# Scheme.net
KiCad netlist of a schematic drawn in Altium Designer
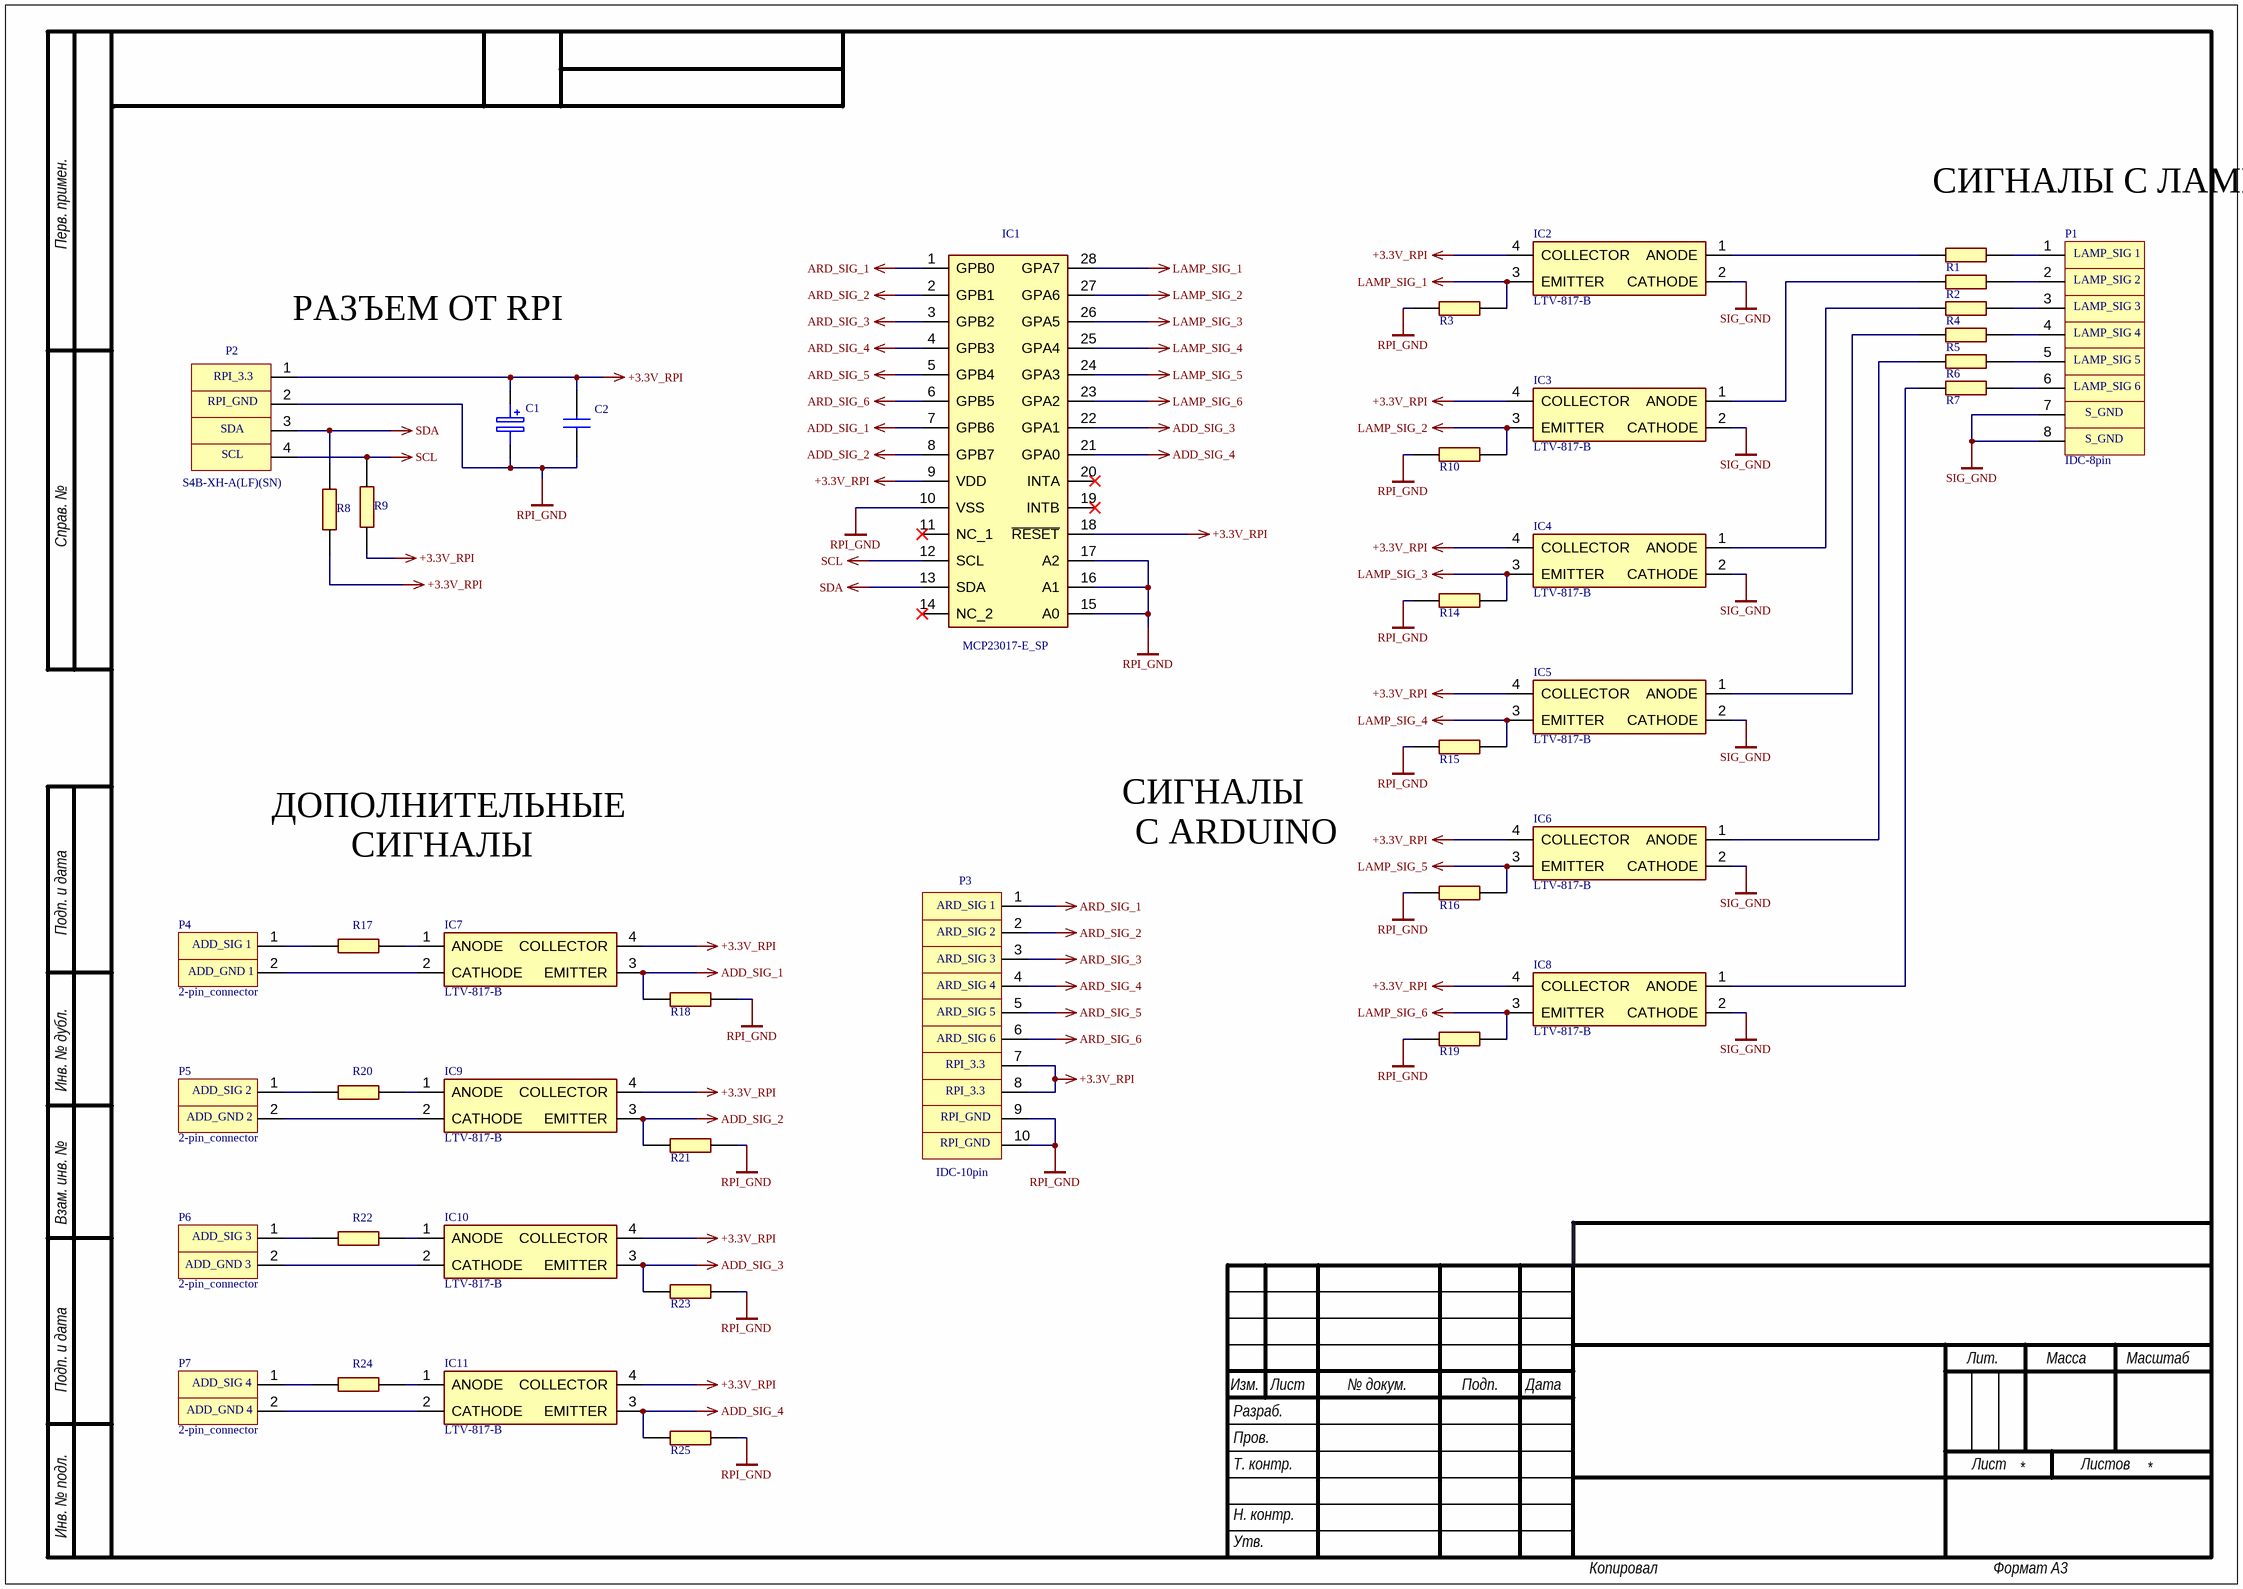
[diagram p0: Scheme.SchDoc]

(export (version "E")
  (design (tool "Eeschema 10.0.6"))
  (components
    (comp (ref "C1")
      (value "EEU-FR1V330")
      (footprint "PcbLib:CAPPRD200W55D500H1250")
      (description "Capacitor Polarised")
      (fields (field (name "MOUSER PART NUMBER") "667-EEU-FR1V330"))
      (libsource (lib "Schlib") (part "EEU-FR1V330"))
    )
    (comp (ref "C2")
      (value "C3216C0G1H683J160AE")
      (footprint "PcbLib:CAPC3216X180N")
      (description "Capacitor")
      (fields (field (name "MOUSER PART NUMBER") "810-C3216C0G1H683J16"))
      (libsource (lib "Schlib") (part "C3216C0G1H683J160AE"))
    )
    (comp (ref "IC1")
      (value "MCP23017-E_SP")
      (footprint "PcbLib:DIP794W56P254L3486H508Q28N")
      (description "Integrated Circuit")
      (fields
        (field (name "MANUFACTURER_PART_NUMBER") "MCP23017-E/SP")
        (field (name "MOUSER PART NUMBER") "579-MCP23017-E/SP")
      )
      (libsource (lib "Schlib") (part "MCP23017-E_SP"))
    )
    (comp (ref "IC2")
      (value "LTV-817-B")
      (footprint "PcbLib:DIP762W60P254L460H420Q4N")
      (description "Integrated Circuit")
      (libsource (lib "Schlib") (part "LTV-817-B"))
    )
    (comp (ref "IC3")
      (value "LTV-817-B")
      (footprint "PcbLib:DIP762W60P254L460H420Q4N")
      (description "Integrated Circuit")
      (libsource (lib "Schlib") (part "LTV-817-B"))
    )
    (comp (ref "IC4")
      (value "LTV-817-B")
      (footprint "PcbLib:DIP762W60P254L460H420Q4N")
      (description "Integrated Circuit")
      (libsource (lib "Schlib") (part "LTV-817-B"))
    )
    (comp (ref "IC5")
      (value "LTV-817-B")
      (footprint "PcbLib:DIP762W60P254L460H420Q4N")
      (description "Integrated Circuit")
      (libsource (lib "Schlib") (part "LTV-817-B"))
    )
    (comp (ref "IC6")
      (value "LTV-817-B")
      (footprint "PcbLib:DIP762W60P254L460H420Q4N")
      (description "Integrated Circuit")
      (libsource (lib "Schlib") (part "LTV-817-B"))
    )
    (comp (ref "IC7")
      (value "LTV-817-B")
      (footprint "PcbLib:DIP762W60P254L460H420Q4N")
      (description "Integrated Circuit")
      (libsource (lib "") (part "LTV-817-B_1"))
    )
    (comp (ref "IC8")
      (value "LTV-817-B")
      (footprint "PcbLib:DIP762W60P254L460H420Q4N")
      (description "Integrated Circuit")
      (libsource (lib "Schlib") (part "LTV-817-B"))
    )
    (comp (ref "IC9")
      (value "LTV-817-B")
      (footprint "PcbLib:DIP762W60P254L460H420Q4N")
      (description "Integrated Circuit")
      (libsource (lib "") (part "LTV-817-B_1"))
    )
    (comp (ref "IC10")
      (value "LTV-817-B")
      (footprint "PcbLib:DIP762W60P254L460H420Q4N")
      (description "Integrated Circuit")
      (libsource (lib "") (part "LTV-817-B_1"))
    )
    (comp (ref "IC11")
      (value "LTV-817-B")
      (footprint "PcbLib:DIP762W60P254L460H420Q4N")
      (description "Integrated Circuit")
      (libsource (lib "") (part "LTV-817-B_1"))
    )
    (comp (ref "P1") (value "IDC-8pin") (footprint "IDC-8pin") (libsource (lib "Schlib") (part "IDC-8pin")))
    (comp (ref "P2")
      (value "S4B-XH-A(LF)(SN)")
      (footprint "JST-S4B-XH-A(LF)(SN)_V")
      (libsource (lib "Schlib") (part "S4B-XH-A(LF)(SN)"))
    )
    (comp (ref "P3")
      (value "IDC-10pin")
      (footprint "IDC-10PIN")
      (libsource (lib "Schlib") (part "IDC-10pin"))
    )
    (comp (ref "P4")
      (value "2-pin_connector")
      (footprint "2-pin_connector")
      (libsource (lib "Schlib") (part "2-pin_connector"))
    )
    (comp (ref "P5")
      (value "2-pin_connector")
      (footprint "2-pin_connector")
      (libsource (lib "Schlib") (part "2-pin_connector"))
    )
    (comp (ref "P6")
      (value "2-pin_connector")
      (footprint "2-pin_connector")
      (libsource (lib "Schlib") (part "2-pin_connector"))
    )
    (comp (ref "P7")
      (value "2-pin_connector")
      (footprint "2-pin_connector")
      (libsource (lib "Schlib") (part "2-pin_connector"))
    )
    (comp (ref "R1")
      (value "CR1206-FW-1504ELF")
      (footprint "PcbLib:RESC3216X75N")
      (description "Resistor")
      (fields (field (name "MOUSER PART NUMBER") "652-CR1206FW1504ELF"))
      (libsource (lib "Schlib") (part "CR1206-FW-1504ELF"))
    )
    (comp (ref "R2")
      (value "CR1206-FW-1504ELF")
      (footprint "PcbLib:RESC3216X75N")
      (description "Resistor")
      (fields (field (name "MOUSER PART NUMBER") "652-CR1206FW1504ELF"))
      (libsource (lib "Schlib") (part "CR1206-FW-1504ELF"))
    )
    (comp (ref "R3")
      (value "CR1206-FW-1504ELF")
      (footprint "PcbLib:RESC3216X75N")
      (description "Resistor")
      (fields (field (name "MOUSER PART NUMBER") "652-CR1206FW1504ELF"))
      (libsource (lib "") (part "CR1206-FW-1504ELF_2"))
    )
    (comp (ref "R4")
      (value "CR1206-FW-1504ELF")
      (footprint "PcbLib:RESC3216X75N")
      (description "Resistor")
      (fields (field (name "MOUSER PART NUMBER") "652-CR1206FW1504ELF"))
      (libsource (lib "Schlib") (part "CR1206-FW-1504ELF"))
    )
    (comp (ref "R5")
      (value "CR1206-FW-1504ELF")
      (footprint "PcbLib:RESC3216X75N")
      (description "Resistor")
      (fields (field (name "MOUSER PART NUMBER") "652-CR1206FW1504ELF"))
      (libsource (lib "Schlib") (part "CR1206-FW-1504ELF"))
    )
    (comp (ref "R6")
      (value "CR1206-FW-1504ELF")
      (footprint "PcbLib:RESC3216X75N")
      (description "Resistor")
      (fields (field (name "MOUSER PART NUMBER") "652-CR1206FW1504ELF"))
      (libsource (lib "Schlib") (part "CR1206-FW-1504ELF"))
    )
    (comp (ref "R7")
      (value "CR1206-FW-1504ELF")
      (footprint "PcbLib:RESC3216X75N")
      (description "Resistor")
      (fields (field (name "MOUSER PART NUMBER") "652-CR1206FW1504ELF"))
      (libsource (lib "Schlib") (part "CR1206-FW-1504ELF"))
    )
    (comp (ref "R8")
      (value "CR1206-FW-1504ELF")
      (footprint "PcbLib:RESC3216X75N")
      (description "Resistor")
      (fields (field (name "MOUSER PART NUMBER") "652-CR1206FW1504ELF"))
      (libsource (lib "") (part "CR1206-FW-1504ELF_2"))
    )
    (comp (ref "R9")
      (value "CR1206-FW-1504ELF")
      (footprint "PcbLib:RESC3216X75N")
      (description "Resistor")
      (fields (field (name "MOUSER PART NUMBER") "652-CR1206FW1504ELF"))
      (libsource (lib "") (part "CR1206-FW-1504ELF_2"))
    )
    (comp (ref "R10")
      (value "CR1206-FW-1504ELF")
      (footprint "PcbLib:RESC3216X75N")
      (description "Resistor")
      (fields (field (name "MOUSER PART NUMBER") "652-CR1206FW1504ELF"))
      (libsource (lib "") (part "CR1206-FW-1504ELF_2"))
    )
    (comp (ref "R14")
      (value "CR1206-FW-1504ELF")
      (footprint "PcbLib:RESC3216X75N")
      (description "Resistor")
      (fields (field (name "MOUSER PART NUMBER") "652-CR1206FW1504ELF"))
      (libsource (lib "") (part "CR1206-FW-1504ELF_2"))
    )
    (comp (ref "R15")
      (value "CR1206-FW-1504ELF")
      (footprint "PcbLib:RESC3216X75N")
      (description "Resistor")
      (fields (field (name "MOUSER PART NUMBER") "652-CR1206FW1504ELF"))
      (libsource (lib "") (part "CR1206-FW-1504ELF_2"))
    )
    (comp (ref "R16")
      (value "CR1206-FW-1504ELF")
      (footprint "PcbLib:RESC3216X75N")
      (description "Resistor")
      (fields (field (name "MOUSER PART NUMBER") "652-CR1206FW1504ELF"))
      (libsource (lib "") (part "CR1206-FW-1504ELF_2"))
    )
    (comp (ref "R17")
      (value "CR1206-FW-1504ELF")
      (footprint "PcbLib:RESC3216X75N")
      (description "Resistor")
      (fields (field (name "MOUSER PART NUMBER") "652-CR1206FW1504ELF"))
      (libsource (lib "Schlib") (part "CR1206-FW-1504ELF"))
    )
    (comp (ref "R18")
      (value "CR1206-FW-1504ELF")
      (footprint "PcbLib:RESC3216X75N")
      (description "Resistor")
      (fields (field (name "MOUSER PART NUMBER") "652-CR1206FW1504ELF"))
      (libsource (lib "") (part "CR1206-FW-1504ELF_1"))
    )
    (comp (ref "R19")
      (value "CR1206-FW-1504ELF")
      (footprint "PcbLib:RESC3216X75N")
      (description "Resistor")
      (fields (field (name "MOUSER PART NUMBER") "652-CR1206FW1504ELF"))
      (libsource (lib "") (part "CR1206-FW-1504ELF_2"))
    )
    (comp (ref "R20")
      (value "CR1206-FW-1504ELF")
      (footprint "PcbLib:RESC3216X75N")
      (description "Resistor")
      (fields (field (name "MOUSER PART NUMBER") "652-CR1206FW1504ELF"))
      (libsource (lib "Schlib") (part "CR1206-FW-1504ELF"))
    )
    (comp (ref "R21")
      (value "CR1206-FW-1504ELF")
      (footprint "PcbLib:RESC3216X75N")
      (description "Resistor")
      (fields (field (name "MOUSER PART NUMBER") "652-CR1206FW1504ELF"))
      (libsource (lib "") (part "CR1206-FW-1504ELF_1"))
    )
    (comp (ref "R22")
      (value "CR1206-FW-1504ELF")
      (footprint "PcbLib:RESC3216X75N")
      (description "Resistor")
      (fields (field (name "MOUSER PART NUMBER") "652-CR1206FW1504ELF"))
      (libsource (lib "Schlib") (part "CR1206-FW-1504ELF"))
    )
    (comp (ref "R23")
      (value "CR1206-FW-1504ELF")
      (footprint "PcbLib:RESC3216X75N")
      (description "Resistor")
      (fields (field (name "MOUSER PART NUMBER") "652-CR1206FW1504ELF"))
      (libsource (lib "") (part "CR1206-FW-1504ELF_1"))
    )
    (comp (ref "R24")
      (value "CR1206-FW-1504ELF")
      (footprint "PcbLib:RESC3216X75N")
      (description "Resistor")
      (fields (field (name "MOUSER PART NUMBER") "652-CR1206FW1504ELF"))
      (libsource (lib "Schlib") (part "CR1206-FW-1504ELF"))
    )
    (comp (ref "R25")
      (value "CR1206-FW-1504ELF")
      (footprint "PcbLib:RESC3216X75N")
      (description "Resistor")
      (fields (field (name "MOUSER PART NUMBER") "652-CR1206FW1504ELF"))
      (libsource (lib "") (part "CR1206-FW-1504ELF_1"))
    )
  )
  (nets
    (net (code "1") (name "+3.3V_RPI") (class "Default")
      (node (ref "C1") (pin "1") (pinfunction "+_1") (pintype "passive"))
      (node (ref "C2") (pin "2") (pinfunction "2_2") (pintype "passive"))
      (node (ref "IC1") (pin "18") (pinfunction "~{RESET}_18") (pintype "passive"))
      (node (ref "IC1") (pin "9") (pinfunction "VDD_9") (pintype "passive"))
      (node (ref "IC10") (pin "4") (pinfunction "COLLECTOR_4") (pintype "passive"))
      (node (ref "IC11") (pin "4") (pinfunction "COLLECTOR_4") (pintype "passive"))
      (node (ref "IC2") (pin "4") (pinfunction "COLLECTOR_4") (pintype "passive"))
      (node (ref "IC3") (pin "4") (pinfunction "COLLECTOR_4") (pintype "passive"))
      (node (ref "IC4") (pin "4") (pinfunction "COLLECTOR_4") (pintype "passive"))
      (node (ref "IC5") (pin "4") (pinfunction "COLLECTOR_4") (pintype "passive"))
      (node (ref "IC6") (pin "4") (pinfunction "COLLECTOR_4") (pintype "passive"))
      (node (ref "IC7") (pin "4") (pinfunction "COLLECTOR_4") (pintype "passive"))
      (node (ref "IC8") (pin "4") (pinfunction "COLLECTOR_4") (pintype "passive"))
      (node (ref "IC9") (pin "4") (pinfunction "COLLECTOR_4") (pintype "passive"))
      (node (ref "P2") (pin "1") (pinfunction "1_1") (pintype "passive"))
      (node (ref "P3") (pin "7") (pinfunction "7_7") (pintype "passive"))
      (node (ref "P3") (pin "8") (pinfunction "8_8") (pintype "passive"))
      (node (ref "R8") (pin "2") (pinfunction "2_2") (pintype "passive"))
      (node (ref "R9") (pin "2") (pinfunction "2_2") (pintype "passive"))
    )
    (net (code "2") (name "ADD_SIG_1") (class "Default")
      (node (ref "IC1") (pin "7") (pinfunction "GPB6_7") (pintype "passive"))
      (node (ref "IC7") (pin "3") (pinfunction "EMITTER_3") (pintype "passive"))
      (node (ref "R18") (pin "1") (pinfunction "1_1") (pintype "passive"))
    )
    (net (code "3") (name "ADD_SIG_2") (class "Default")
      (node (ref "IC1") (pin "8") (pinfunction "GPB7_8") (pintype "passive"))
      (node (ref "IC9") (pin "3") (pinfunction "EMITTER_3") (pintype "passive"))
      (node (ref "R21") (pin "1") (pinfunction "1_1") (pintype "passive"))
    )
    (net (code "4") (name "ADD_SIG_3") (class "Default")
      (node (ref "IC1") (pin "22") (pinfunction "GPA1_22") (pintype "passive"))
      (node (ref "IC10") (pin "3") (pinfunction "EMITTER_3") (pintype "passive"))
      (node (ref "R23") (pin "1") (pinfunction "1_1") (pintype "passive"))
    )
    (net (code "5") (name "ADD_SIG_4") (class "Default")
      (node (ref "IC1") (pin "21") (pinfunction "GPA0_21") (pintype "passive"))
      (node (ref "IC11") (pin "3") (pinfunction "EMITTER_3") (pintype "passive"))
      (node (ref "R25") (pin "1") (pinfunction "1_1") (pintype "passive"))
    )
    (net (code "6") (name "ARD_SIG_1") (class "Default")
      (node (ref "IC1") (pin "1") (pinfunction "GPB0_1") (pintype "passive"))
      (node (ref "P3") (pin "1") (pinfunction "1_1") (pintype "passive"))
    )
    (net (code "7") (name "ARD_SIG_2") (class "Default")
      (node (ref "IC1") (pin "2") (pinfunction "GPB1_2") (pintype "passive"))
      (node (ref "P3") (pin "2") (pinfunction "2_2") (pintype "passive"))
    )
    (net (code "8") (name "ARD_SIG_3") (class "Default")
      (node (ref "IC1") (pin "3") (pinfunction "GPB2_3") (pintype "passive"))
      (node (ref "P3") (pin "3") (pinfunction "3_3") (pintype "passive"))
    )
    (net (code "9") (name "ARD_SIG_4") (class "Default")
      (node (ref "IC1") (pin "4") (pinfunction "GPB3_4") (pintype "passive"))
      (node (ref "P3") (pin "4") (pinfunction "4_4") (pintype "passive"))
    )
    (net (code "10") (name "ARD_SIG_5") (class "Default")
      (node (ref "IC1") (pin "5") (pinfunction "GPB4_5") (pintype "passive"))
      (node (ref "P3") (pin "5") (pinfunction "5_5") (pintype "passive"))
    )
    (net (code "11") (name "ARD_SIG_6") (class "Default")
      (node (ref "IC1") (pin "6") (pinfunction "GPB5_6") (pintype "passive"))
      (node (ref "P3") (pin "6") (pinfunction "6_6") (pintype "passive"))
    )
    (net (code "12") (name "LAMP_SIG_1") (class "Default")
      (node (ref "IC1") (pin "28") (pinfunction "GPA7_28") (pintype "passive"))
      (node (ref "IC2") (pin "3") (pinfunction "EMITTER_3") (pintype "passive"))
      (node (ref "R3") (pin "1") (pinfunction "1_1") (pintype "passive"))
    )
    (net (code "13") (name "LAMP_SIG_2") (class "Default")
      (node (ref "IC1") (pin "27") (pinfunction "GPA6_27") (pintype "passive"))
      (node (ref "IC3") (pin "3") (pinfunction "EMITTER_3") (pintype "passive"))
      (node (ref "R10") (pin "1") (pinfunction "1_1") (pintype "passive"))
    )
    (net (code "14") (name "LAMP_SIG_3") (class "Default")
      (node (ref "IC1") (pin "26") (pinfunction "GPA5_26") (pintype "passive"))
      (node (ref "IC4") (pin "3") (pinfunction "EMITTER_3") (pintype "passive"))
      (node (ref "R14") (pin "1") (pinfunction "1_1") (pintype "passive"))
    )
    (net (code "15") (name "LAMP_SIG_4") (class "Default")
      (node (ref "IC1") (pin "25") (pinfunction "GPA4_25") (pintype "passive"))
      (node (ref "IC5") (pin "3") (pinfunction "EMITTER_3") (pintype "passive"))
      (node (ref "R15") (pin "1") (pinfunction "1_1") (pintype "passive"))
    )
    (net (code "16") (name "LAMP_SIG_5") (class "Default")
      (node (ref "IC1") (pin "24") (pinfunction "GPA3_24") (pintype "passive"))
      (node (ref "IC6") (pin "3") (pinfunction "EMITTER_3") (pintype "passive"))
      (node (ref "R16") (pin "1") (pinfunction "1_1") (pintype "passive"))
    )
    (net (code "17") (name "LAMP_SIG_6") (class "Default")
      (node (ref "IC1") (pin "23") (pinfunction "GPA2_23") (pintype "passive"))
      (node (ref "IC8") (pin "3") (pinfunction "EMITTER_3") (pintype "passive"))
      (node (ref "R19") (pin "1") (pinfunction "1_1") (pintype "passive"))
    )
    (net (code "18") (name "Net-(IC2-ANODE)") (class "Default")
      (node (ref "IC2") (pin "1") (pinfunction "ANODE_1") (pintype "passive"))
      (node (ref "R1") (pin "1") (pinfunction "1_1") (pintype "passive"))
    )
    (net (code "19") (name "Net-(IC3-ANODE)") (class "Default")
      (node (ref "IC3") (pin "1") (pinfunction "ANODE_1") (pintype "passive"))
      (node (ref "R2") (pin "1") (pinfunction "1_1") (pintype "passive"))
    )
    (net (code "20") (name "Net-(IC4-ANODE)") (class "Default")
      (node (ref "IC4") (pin "1") (pinfunction "ANODE_1") (pintype "passive"))
      (node (ref "R4") (pin "1") (pinfunction "1_1") (pintype "passive"))
    )
    (net (code "21") (name "Net-(IC5-ANODE)") (class "Default")
      (node (ref "IC5") (pin "1") (pinfunction "ANODE_1") (pintype "passive"))
      (node (ref "R5") (pin "1") (pinfunction "1_1") (pintype "passive"))
    )
    (net (code "22") (name "Net-(IC6-ANODE)") (class "Default")
      (node (ref "IC6") (pin "1") (pinfunction "ANODE_1") (pintype "passive"))
      (node (ref "R6") (pin "1") (pinfunction "1_1") (pintype "passive"))
    )
    (net (code "23") (name "Net-(IC7-ANODE)") (class "Default")
      (node (ref "IC7") (pin "1") (pinfunction "ANODE_1") (pintype "passive"))
      (node (ref "R17") (pin "2") (pinfunction "2_2") (pintype "passive"))
    )
    (net (code "24") (name "Net-(IC7-CATHODE)") (class "Default")
      (node (ref "IC7") (pin "2") (pinfunction "CATHODE_2") (pintype "passive"))
      (node (ref "P4") (pin "2") (pinfunction "2_2") (pintype "passive"))
    )
    (net (code "25") (name "Net-(IC8-ANODE)") (class "Default")
      (node (ref "IC8") (pin "1") (pinfunction "ANODE_1") (pintype "passive"))
      (node (ref "R7") (pin "1") (pinfunction "1_1") (pintype "passive"))
    )
    (net (code "26") (name "Net-(IC9-ANODE)") (class "Default")
      (node (ref "IC9") (pin "1") (pinfunction "ANODE_1") (pintype "passive"))
      (node (ref "R20") (pin "2") (pinfunction "2_2") (pintype "passive"))
    )
    (net (code "27") (name "Net-(IC9-CATHODE)") (class "Default")
      (node (ref "IC9") (pin "2") (pinfunction "CATHODE_2") (pintype "passive"))
      (node (ref "P5") (pin "2") (pinfunction "2_2") (pintype "passive"))
    )
    (net (code "28") (name "Net-(IC10-ANODE)") (class "Default")
      (node (ref "IC10") (pin "1") (pinfunction "ANODE_1") (pintype "passive"))
      (node (ref "R22") (pin "2") (pinfunction "2_2") (pintype "passive"))
    )
    (net (code "29") (name "Net-(IC10-CATHODE)") (class "Default")
      (node (ref "IC10") (pin "2") (pinfunction "CATHODE_2") (pintype "passive"))
      (node (ref "P6") (pin "2") (pinfunction "2_2") (pintype "passive"))
    )
    (net (code "30") (name "Net-(IC11-ANODE)") (class "Default")
      (node (ref "IC11") (pin "1") (pinfunction "ANODE_1") (pintype "passive"))
      (node (ref "R24") (pin "2") (pinfunction "2_2") (pintype "passive"))
    )
    (net (code "31") (name "Net-(IC11-CATHODE)") (class "Default")
      (node (ref "IC11") (pin "2") (pinfunction "CATHODE_2") (pintype "passive"))
      (node (ref "P7") (pin "2") (pinfunction "2_2") (pintype "passive"))
    )
    (net (code "32") (name "Net-(P1-Pad1)") (class "Default")
      (node (ref "P1") (pin "1") (pinfunction "1_1") (pintype "passive"))
      (node (ref "R1") (pin "2") (pinfunction "2_2") (pintype "passive"))
    )
    (net (code "33") (name "Net-(P1-Pad2)") (class "Default")
      (node (ref "P1") (pin "2") (pinfunction "2_2") (pintype "passive"))
      (node (ref "R2") (pin "2") (pinfunction "2_2") (pintype "passive"))
    )
    (net (code "34") (name "Net-(P1-Pad3)") (class "Default")
      (node (ref "P1") (pin "3") (pinfunction "3_3") (pintype "passive"))
      (node (ref "R4") (pin "2") (pinfunction "2_2") (pintype "passive"))
    )
    (net (code "35") (name "Net-(P1-Pad4)") (class "Default")
      (node (ref "P1") (pin "4") (pinfunction "4_4") (pintype "passive"))
      (node (ref "R5") (pin "2") (pinfunction "2_2") (pintype "passive"))
    )
    (net (code "36") (name "Net-(P1-Pad5)") (class "Default")
      (node (ref "P1") (pin "5") (pinfunction "5_5") (pintype "passive"))
      (node (ref "R6") (pin "2") (pinfunction "2_2") (pintype "passive"))
    )
    (net (code "37") (name "Net-(P1-Pad6)") (class "Default")
      (node (ref "P1") (pin "6") (pinfunction "6_6") (pintype "passive"))
      (node (ref "R7") (pin "2") (pinfunction "2_2") (pintype "passive"))
    )
    (net (code "38") (name "Net-(P4-Pad1)") (class "Default")
      (node (ref "P4") (pin "1") (pinfunction "1_1") (pintype "passive"))
      (node (ref "R17") (pin "1") (pinfunction "1_1") (pintype "passive"))
    )
    (net (code "39") (name "Net-(P5-Pad1)") (class "Default")
      (node (ref "P5") (pin "1") (pinfunction "1_1") (pintype "passive"))
      (node (ref "R20") (pin "1") (pinfunction "1_1") (pintype "passive"))
    )
    (net (code "40") (name "Net-(P6-Pad1)") (class "Default")
      (node (ref "P6") (pin "1") (pinfunction "1_1") (pintype "passive"))
      (node (ref "R22") (pin "1") (pinfunction "1_1") (pintype "passive"))
    )
    (net (code "41") (name "Net-(P7-Pad1)") (class "Default")
      (node (ref "P7") (pin "1") (pinfunction "1_1") (pintype "passive"))
      (node (ref "R24") (pin "1") (pinfunction "1_1") (pintype "passive"))
    )
    (net (code "42") (name "RPI_GND") (class "Default")
      (node (ref "C1") (pin "2") (pinfunction "-_2") (pintype "passive"))
      (node (ref "C2") (pin "1") (pinfunction "1_1") (pintype "passive"))
      (node (ref "IC1") (pin "10") (pinfunction "VSS_10") (pintype "passive"))
      (node (ref "IC1") (pin "15") (pinfunction "A0_15") (pintype "passive"))
      (node (ref "IC1") (pin "16") (pinfunction "A1_16") (pintype "passive"))
      (node (ref "IC1") (pin "17") (pinfunction "A2_17") (pintype "passive"))
      (node (ref "P2") (pin "2") (pinfunction "2_2") (pintype "passive"))
      (node (ref "P3") (pin "10") (pinfunction "8_10") (pintype "passive"))
      (node (ref "P3") (pin "9") (pinfunction "7_9") (pintype "passive"))
      (node (ref "R10") (pin "2") (pinfunction "2_2") (pintype "passive"))
      (node (ref "R14") (pin "2") (pinfunction "2_2") (pintype "passive"))
      (node (ref "R15") (pin "2") (pinfunction "2_2") (pintype "passive"))
      (node (ref "R16") (pin "2") (pinfunction "2_2") (pintype "passive"))
      (node (ref "R18") (pin "2") (pinfunction "2_2") (pintype "passive"))
      (node (ref "R19") (pin "2") (pinfunction "2_2") (pintype "passive"))
      (node (ref "R21") (pin "2") (pinfunction "2_2") (pintype "passive"))
      (node (ref "R23") (pin "2") (pinfunction "2_2") (pintype "passive"))
      (node (ref "R25") (pin "2") (pinfunction "2_2") (pintype "passive"))
      (node (ref "R3") (pin "2") (pinfunction "2_2") (pintype "passive"))
    )
    (net (code "43") (name "SCL") (class "Default")
      (node (ref "IC1") (pin "12") (pinfunction "SCL_12") (pintype "passive"))
      (node (ref "P2") (pin "4") (pinfunction "4_4") (pintype "passive"))
      (node (ref "R9") (pin "1") (pinfunction "1_1") (pintype "passive"))
    )
    (net (code "44") (name "SDA") (class "Default")
      (node (ref "IC1") (pin "13") (pinfunction "SDA_13") (pintype "passive"))
      (node (ref "P2") (pin "3") (pinfunction "3_3") (pintype "passive"))
      (node (ref "R8") (pin "1") (pinfunction "1_1") (pintype "passive"))
    )
    (net (code "45") (name "SIG_GND") (class "Default")
      (node (ref "IC2") (pin "2") (pinfunction "CATHODE_2") (pintype "passive"))
      (node (ref "IC3") (pin "2") (pinfunction "CATHODE_2") (pintype "passive"))
      (node (ref "IC4") (pin "2") (pinfunction "CATHODE_2") (pintype "passive"))
      (node (ref "IC5") (pin "2") (pinfunction "CATHODE_2") (pintype "passive"))
      (node (ref "IC6") (pin "2") (pinfunction "CATHODE_2") (pintype "passive"))
      (node (ref "IC8") (pin "2") (pinfunction "CATHODE_2") (pintype "passive"))
      (node (ref "P1") (pin "7") (pinfunction "7_7") (pintype "passive"))
      (node (ref "P1") (pin "8") (pinfunction "8_8") (pintype "passive"))
    )
    (net (code "46") (name "unconnected-(IC1-INTA-Pad20)") (class "Default")
      (node (ref "IC1") (pin "20") (pinfunction "INTA_20") (pintype "passive+no_connect"))
    )
    (net (code "47") (name "unconnected-(IC1-INTB-Pad19)") (class "Default")
      (node (ref "IC1") (pin "19") (pinfunction "INTB_19") (pintype "passive+no_connect"))
    )
    (net (code "48") (name "unconnected-(IC1-NC_1-Pad11)") (class "Default")
      (node (ref "IC1") (pin "11") (pinfunction "NC_1_11") (pintype "passive+no_connect"))
    )
    (net (code "49") (name "unconnected-(IC1-NC_2-Pad14)") (class "Default")
      (node (ref "IC1") (pin "14") (pinfunction "NC_2_14") (pintype "passive+no_connect"))
    )
  )
)
